# TIDA-01576_ADS8686S_ISO_Interface_Pg4-Is.net
KiCad netlist of a schematic drawn in Altium Designer
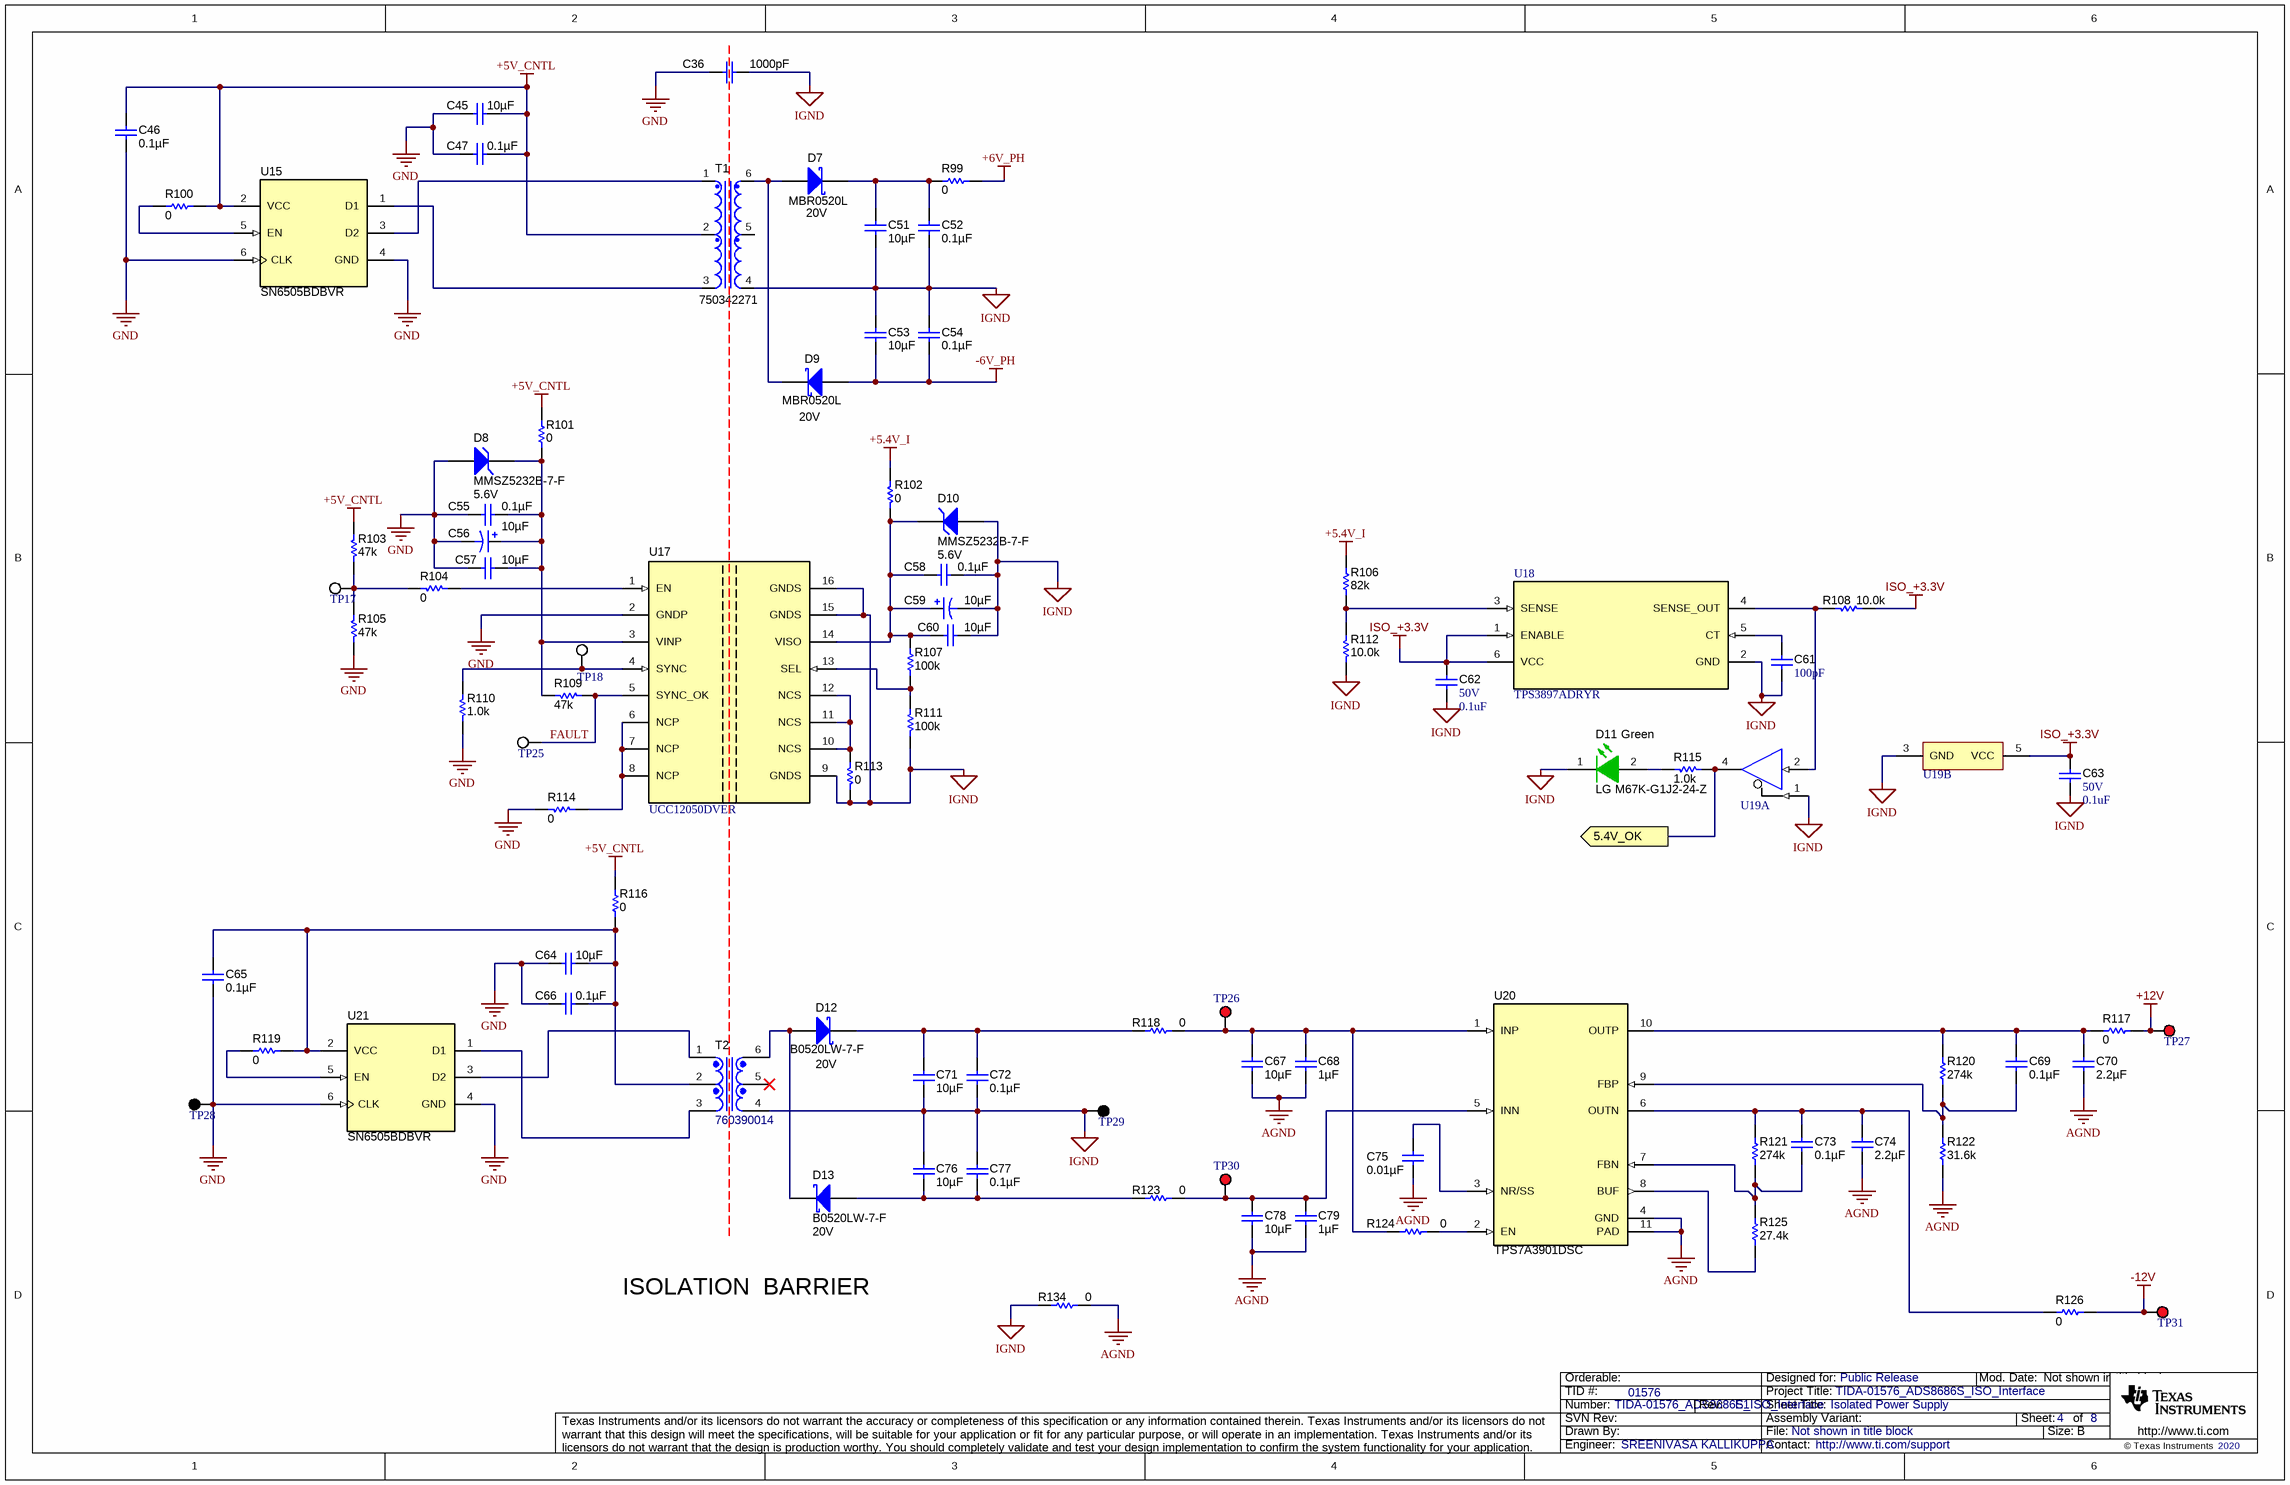
[diagram p0: TIDA-01576_ADS8686S_ISO_Interface_Pg4-Isolated Power Supply.SchDoc]

(export (version "E")
  (design (tool "Eeschema 10.0.6"))
  (components
    (comp (ref "C36")
      (value "1000pF")
      (footprint "CAP_200mil")
      (description "CAP CER 1000PF 1KV 10% RADIAL")
      (fields
        (field (name "PARTNUMBER") "S102K29Y5PN63J5R")
        (field (name "MANUFACTURER") "Vishay BC Components")
        (field (name "PUBLISHER") "Texas Instruments")
      )
      (libsource (lib "TI-INDIA-ALTIUM") (part "202R18W102KV4E"))
    )
    (comp (ref "C45")
      (value "~")
      (footprint "1210")
      (description "CAP, CERM, 10uF, 35V, +/-20%, X7R, 1210")
      (fields
        (field (name "PARTNUMBER") "GMK325AB7106MM-T")
        (field (name "VALUEDISPLAYED") "10µF")
        (field (name "MANUFACTURER") "Taiyo Yuden")
        (field (name "PUBLISHER") "Texas Instruments")
      )
      (libsource (lib "Capacitor_Ceramic") (part "GMK325AB7106MM-T"))
    )
    (comp (ref "C46")
      (value "~")
      (footprint "0603")
      (description "CAP, CERM, 0.1uF, 50V, +/-10%, X7R, 0603")
      (fields
        (field (name "PARTNUMBER") "C0603C104K5RACTU")
        (field (name "VALUEDISPLAYED") "0.1µF")
        (field (name "MANUFACTURER") "Kemet")
        (field (name "PUBLISHER") "Texas Instruments")
      )
      (libsource (lib "Capacitor_Ceramic") (part "C0603C104K5RACTU"))
    )
    (comp (ref "C47")
      (value "~")
      (footprint "0603")
      (description "CAP, CERM, 0.1uF, 50V, +/-10%, X7R, 0603")
      (fields
        (field (name "PARTNUMBER") "C0603C104K5RACTU")
        (field (name "VALUEDISPLAYED") "0.1µF")
        (field (name "MANUFACTURER") "Kemet")
        (field (name "PUBLISHER") "Texas Instruments")
      )
      (libsource (lib "Capacitor_Ceramic") (part "C0603C104K5RACTU"))
    )
    (comp (ref "C51")
      (value "~")
      (footprint "1210")
      (description "CAP, CERM, 10uF, 35V, +/-20%, X7R, 1210")
      (fields
        (field (name "PARTNUMBER") "GMK325AB7106MM-T")
        (field (name "VALUEDISPLAYED") "10µF")
        (field (name "MANUFACTURER") "Taiyo Yuden")
        (field (name "PUBLISHER") "Texas Instruments")
      )
      (libsource (lib "Capacitor_Ceramic") (part "GMK325AB7106MM-T"))
    )
    (comp (ref "C52")
      (value "~")
      (footprint "0603_HV")
      (description "CAP, CERM, 0.1uF, 50V, +/-10%, X7R, 0603")
      (fields
        (field (name "PARTNUMBER") "C0603C104K5RACTU")
        (field (name "VALUEDISPLAYED") "0.1µF")
        (field (name "MANUFACTURER") "Kemet")
        (field (name "PUBLISHER") "Texas Instruments")
      )
      (libsource (lib "Capacitor_Ceramic") (part "C0603C104K5RACTU"))
    )
    (comp (ref "C53")
      (value "~")
      (footprint "1210")
      (description "CAP, CERM, 10uF, 35V, +/-20%, X7R, 1210")
      (fields
        (field (name "PARTNUMBER") "GMK325AB7106MM-T")
        (field (name "VALUEDISPLAYED") "10µF")
        (field (name "MANUFACTURER") "Taiyo Yuden")
        (field (name "PUBLISHER") "Texas Instruments")
      )
      (libsource (lib "Capacitor_Ceramic") (part "GMK325AB7106MM-T"))
    )
    (comp (ref "C54")
      (value "~")
      (footprint "0603_HV")
      (description "CAP, CERM, 0.1uF, 50V, +/-10%, X7R, 0603")
      (fields
        (field (name "PARTNUMBER") "C0603C104K5RACTU")
        (field (name "VALUEDISPLAYED") "0.1µF")
        (field (name "MANUFACTURER") "Kemet")
        (field (name "PUBLISHER") "Texas Instruments")
      )
      (libsource (lib "Capacitor_Ceramic") (part "C0603C104K5RACTU"))
    )
    (comp (ref "C55")
      (value "C0603C104K5RACTU")
      (footprint "0603")
      (description "CAP, CERM, 0.1uF, 50V, +/-10%, X7R, 0603")
      (fields
        (field (name "VALUEDISPLAYED") "0.1µF")
        (field (name "MANUFACTURER") "Kemet")
        (field (name "PUBLISHER") "Texas Instruments")
      )
      (libsource (lib "Capacitor_Ceramic") (part "C0603C104K5RACTU"))
    )
    (comp (ref "C56")
      (value "T491B106K016AT")
      (footprint "3528-21")
      (description "CAP, TA, 10 µF, 16 V, +/- 10%, 2 ohm, SMD")
      (fields
        (field (name "MANUFACTURER") "Vishay-Sprague")
        (field (name "VALUEDISPLAYED") "10µF")
        (field (name "PUBLISHER") "Texas Instruments")
      )
      (libsource (lib "") (part "293D106X9016B2TE3_1"))
    )
    (comp (ref "C57")
      (value "GRM31CR61H106KA12L")
      (footprint "1206_180")
      (description "CAP, CERM, 10 µF, 50 V, +/- 10%, X5R, 1206")
      (fields
        (field (name "VALUEDISPLAYED") "10µF")
        (field (name "MANUFACTURER") "MuRata")
        (field (name "PUBLISHER") "Texas Instruments")
      )
      (libsource (lib "Capacitor_Ceramic") (part "GRM31CR61H106KA12L"))
    )
    (comp (ref "C58")
      (value "C0603C104K5RACTU")
      (footprint "0603")
      (description "CAP, CERM, 0.1uF, 50V, +/-10%, X7R, 0603")
      (fields
        (field (name "VALUEDISPLAYED") "0.1µF")
        (field (name "MANUFACTURER") "Kemet")
        (field (name "PUBLISHER") "Texas Instruments")
      )
      (libsource (lib "Capacitor_Ceramic") (part "C0603C104K5RACTU"))
    )
    (comp (ref "C59")
      (value "T491B106K016AT")
      (footprint "3528-21")
      (description "CAP, TA, 10 µF, 16 V, +/- 10%, 2 ohm, SMD")
      (fields
        (field (name "MANUFACTURER") "Vishay-Sprague")
        (field (name "VALUEDISPLAYED") "10µF")
        (field (name "PUBLISHER") "Texas Instruments")
      )
      (libsource (lib "Combo_Module_TIDA-00170") (part "293D106X9016B2TE3"))
    )
    (comp (ref "C60")
      (value "GRM31CR61H106KA12L")
      (footprint "1206_180")
      (description "CAP, CERM, 10 µF, 50 V, +/- 10%, X5R, 1206")
      (fields
        (field (name "VALUEDISPLAYED") "10µF")
        (field (name "MANUFACTURER") "MuRata")
        (field (name "PUBLISHER") "Texas Instruments")
      )
      (libsource (lib "Capacitor_Ceramic") (part "GRM31CR61H106KA12L"))
    )
    (comp (ref "C61")
      (value "06035A101FAT2A")
      (footprint "0603")
      (description "CAP, CERM, 100 pF, 50 V, +/- 1%, C0G/NP0, 0603")
      (fields
        (field (name "MANUFACTURER") "AVX")
        (field (name "VALUEDISPLAYED") "100pF")
        (field (name "PUBLISHER") "Texas Instruments")
      )
      (libsource (lib "Altium Vault - TI") (part "Capacitor"))
    )
    (comp (ref "C62")
      (value "C0603C104K5RACTU")
      (footprint "0603")
      (description "CAP, CERM, 0.1 uF, 50 V, +/- 10%, X7R, 0603")
      (fields
        (field (name "MANUFACTURER") "Kemet")
        (field (name "VDC_V") "50V")
        (field (name "VALUEDISPLAYED") "0.1uF")
        (field (name "PUBLISHER") "Texas Instruments")
      )
      (libsource (lib "Altium Vault - TI") (part "Capacitor"))
    )
    (comp (ref "C63")
      (value "C0603C104K5RACTU")
      (footprint "0603")
      (description "CAP, CERM, 0.1 uF, 50 V, +/- 10%, X7R, 0603")
      (fields
        (field (name "MANUFACTURER") "Kemet")
        (field (name "VDC_V") "50V")
        (field (name "VALUEDISPLAYED") "0.1uF")
        (field (name "PUBLISHER") "Texas Instruments")
      )
      (libsource (lib "Altium Vault - TI") (part "Capacitor"))
    )
    (comp (ref "C64")
      (value "~")
      (footprint "1210")
      (description "CAP, CERM, 10uF, 35V, +/-20%, X7R, 1210")
      (fields
        (field (name "PARTNUMBER") "GMK325AB7106MM-T")
        (field (name "VALUEDISPLAYED") "10µF")
        (field (name "MANUFACTURER") "Taiyo Yuden")
        (field (name "PUBLISHER") "Texas Instruments")
      )
      (libsource (lib "Capacitor_Ceramic") (part "GMK325AB7106MM-T"))
    )
    (comp (ref "C65")
      (value "~")
      (footprint "0603")
      (description "CAP, CERM, 0.1uF, 50V, +/-10%, X7R, 0603")
      (fields
        (field (name "PARTNUMBER") "C0603C104K5RACTU")
        (field (name "VALUEDISPLAYED") "0.1µF")
        (field (name "MANUFACTURER") "Kemet")
        (field (name "PUBLISHER") "Texas Instruments")
      )
      (libsource (lib "Capacitor_Ceramic") (part "C0603C104K5RACTU"))
    )
    (comp (ref "C66")
      (value "~")
      (footprint "0603")
      (description "CAP, CERM, 0.1uF, 50V, +/-10%, X7R, 0603")
      (fields
        (field (name "PARTNUMBER") "C0603C104K5RACTU")
        (field (name "VALUEDISPLAYED") "0.1µF")
        (field (name "MANUFACTURER") "Kemet")
        (field (name "PUBLISHER") "Texas Instruments")
      )
      (libsource (lib "Capacitor_Ceramic") (part "C0603C104K5RACTU"))
    )
    (comp (ref "C67")
      (value "C1210C106M5RACTU")
      (footprint "1206_180")
      (description "CAP, CERM, 10µF ±20% 50V Ceramic Capacitor X7R 1210")
      (fields
        (field (name "VALUEDISPLAYED") "10µF")
        (field (name "MANUFACTURER") "Kemet")
        (field (name "PUBLISHER") "Texas Instruments")
      )
      (libsource (lib "Capacitor_Ceramic") (part "CL31B106KBHNNNE"))
    )
    (comp (ref "C68")
      (value "C1608X7R1E105K080AB")
      (footprint "0603")
      (description "CAP, CERM,  1µF ±10% 25V Ceramic Capacitor X7R 0603")
      (fields
        (field (name "VALUEDISPLAYED") "1µF")
        (field (name "MANUFACTURER") "TDK")
        (field (name "PUBLISHER") "Texas Instruments")
      )
      (libsource (lib "Capacitor_Ceramic") (part "885012206052"))
    )
    (comp (ref "C69")
      (value "GMK107BJ104KAHT")
      (footprint "0603")
      (description "0.1µF ±10% 35V Ceramic Capacitor X5R 0603")
      (fields
        (field (name "VALUEDISPLAYED") "0.1µF")
        (field (name "MANUFACTURER") "Taiyo Yuden")
        (field (name "PUBLISHER") "Texas Instruments")
      )
      (libsource (lib "Capacitor_Ceramic") (part "06033C104JAT2A"))
    )
    (comp (ref "C70")
      (value "C0805C225K8RACTU")
      (footprint "0805_HV")
      (description "CAP, CERM, 2.2uF, 10V, +/-10%, X7R, 0805")
      (fields
        (field (name "VALUEDISPLAYED") "2.2µF")
        (field (name "MANUFACTURER") "Kemet")
        (field (name "PUBLISHER") "Texas Instruments")
      )
      (libsource (lib "Capacitor_Ceramic") (part "C0805C225K8RACTU"))
    )
    (comp (ref "C71")
      (value "~")
      (footprint "1210")
      (description "CAP, CERM, 10uF, 35V, +/-20%, X7R, 1210")
      (fields
        (field (name "PARTNUMBER") "GMK325AB7106MM-T")
        (field (name "VALUEDISPLAYED") "10µF")
        (field (name "MANUFACTURER") "Taiyo Yuden")
        (field (name "PUBLISHER") "Texas Instruments")
      )
      (libsource (lib "Capacitor_Ceramic") (part "GMK325AB7106MM-T"))
    )
    (comp (ref "C72")
      (value "~")
      (footprint "0603")
      (description "CAP, CERM, 0.1uF, 50V, +/-10%, X7R, 0603")
      (fields
        (field (name "PARTNUMBER") "C0603C104K5RACTU")
        (field (name "VALUEDISPLAYED") "0.1µF")
        (field (name "MANUFACTURER") "Kemet")
        (field (name "PUBLISHER") "Texas Instruments")
      )
      (libsource (lib "Capacitor_Ceramic") (part "C0603C104K5RACTU"))
    )
    (comp (ref "C73")
      (value "GMK107BJ104KAHT")
      (footprint "0603")
      (description "0.1µF ±10% 35V Ceramic Capacitor X5R 0603")
      (fields
        (field (name "VALUEDISPLAYED") "0.1µF")
        (field (name "MANUFACTURER") "Taiyo Yuden")
        (field (name "PUBLISHER") "Texas Instruments")
      )
      (libsource (lib "Capacitor_Ceramic") (part "06033C104JAT2A"))
    )
    (comp (ref "C74")
      (value "C0805C225K8RACTU")
      (footprint "0805_HV")
      (description "CAP, CERM, 2.2uF, 10V, +/-10%, X7R, 0805")
      (fields
        (field (name "VALUEDISPLAYED") "2.2µF")
        (field (name "MANUFACTURER") "Kemet")
        (field (name "PUBLISHER") "Texas Instruments")
      )
      (libsource (lib "Capacitor_Ceramic") (part "C0805C225K8RACTU"))
    )
    (comp (ref "C75")
      (value "GRM188R70J103KA01D")
      (footprint "0603")
      (description "CAP, CERM, 0.01 µF, 6.3 V, +/- 10%, X7R, 0603")
      (fields
        (field (name "VALUEDISPLAYED") "0.01µF")
        (field (name "MANUFACTURER") "MuRata")
        (field (name "PUBLISHER") "Texas Instruments")
      )
      (libsource (lib "Capacitor_Ceramic") (part "GRM188R70J103KA01D"))
    )
    (comp (ref "C76")
      (value "~")
      (footprint "1210")
      (description "CAP, CERM, 10uF, 35V, +/-20%, X7R, 1210")
      (fields
        (field (name "PARTNUMBER") "GMK325AB7106MM-T")
        (field (name "VALUEDISPLAYED") "10µF")
        (field (name "MANUFACTURER") "Taiyo Yuden")
        (field (name "PUBLISHER") "Texas Instruments")
      )
      (libsource (lib "Capacitor_Ceramic") (part "GMK325AB7106MM-T"))
    )
    (comp (ref "C77")
      (value "~")
      (footprint "0603")
      (description "CAP, CERM, 0.1uF, 50V, +/-10%, X7R, 0603")
      (fields
        (field (name "PARTNUMBER") "C0603C104K5RACTU")
        (field (name "VALUEDISPLAYED") "0.1µF")
        (field (name "MANUFACTURER") "Kemet")
        (field (name "PUBLISHER") "Texas Instruments")
      )
      (libsource (lib "Capacitor_Ceramic") (part "C0603C104K5RACTU"))
    )
    (comp (ref "C78")
      (value "C1210C106M5RACTU")
      (footprint "1206_180")
      (description "CAP, CERM, 10µF ±20% 50V Ceramic Capacitor X7R 1210")
      (fields
        (field (name "VALUEDISPLAYED") "10µF")
        (field (name "MANUFACTURER") "Kemet")
        (field (name "PUBLISHER") "Texas Instruments")
      )
      (libsource (lib "Capacitor_Ceramic") (part "CL31B106KBHNNNE"))
    )
    (comp (ref "C79")
      (value "C1608X7R1E105K080AB")
      (footprint "0603")
      (description "CAP, CERM,  1µF ±10% 25V Ceramic Capacitor X7R 0603")
      (fields
        (field (name "VALUEDISPLAYED") "1µF")
        (field (name "MANUFACTURER") "TDK")
        (field (name "PUBLISHER") "Texas Instruments")
      )
      (libsource (lib "Capacitor_Ceramic") (part "885012206052"))
    )
    (comp (ref "D7")
      (value "MBR0520L")
      (footprint "SOD-123")
      (description "Diode, Schottky, 20V, 0.5A, SOD-123")
      (fields
        (field (name "ALTIUM_VALUE") "20V")
        (field (name "MANUFACTURER") "Fairchild Semiconductor")
        (field (name "PUBLISHER") "Texas Instruments")
      )
      (libsource (lib "Diode") (part "MBR0520LT1G"))
    )
    (comp (ref "D8")
      (value "MMSZ5232B-7-F")
      (footprint "SOD-123")
      (description "Diode, Zener, 5.6 V, 500 mW, SOD-123")
      (fields
        (field (name "ALTIUM_VALUE") "5.6V")
        (field (name "MANUFACTURER") "Diodes Inc.")
        (field (name "SYMBOLCREATOR") "a0412235")
        (field (name "PUBLISHER") "Texas Instruments")
      )
      (libsource (lib "ZenerDiodes") (part "MMSZ5232B-7-F"))
    )
    (comp (ref "D9")
      (value "MBR0520L")
      (footprint "SOD-123")
      (description "Diode, Schottky, 20V, 0.5A, SOD-123")
      (fields
        (field (name "ALTIUM_VALUE") "20V")
        (field (name "MANUFACTURER") "Fairchild Semiconductor")
        (field (name "PUBLISHER") "Texas Instruments")
      )
      (libsource (lib "Diode") (part "MBR0520LT1G"))
    )
    (comp (ref "D10")
      (value "MMSZ5232B-7-F")
      (footprint "SOD-123")
      (description "Diode, Zener, 5.6 V, 500 mW, SOD-123")
      (fields
        (field (name "ALTIUM_VALUE") "5.6V")
        (field (name "MANUFACTURER") "Diodes Inc.")
        (field (name "SYMBOLCREATOR") "a0412235")
        (field (name "PUBLISHER") "Texas Instruments")
      )
      (libsource (lib "ZenerDiodes") (part "MMSZ5232B-7-F"))
    )
    (comp (ref "D11")
      (value "LG M67K-G1J2-24-Z")
      (footprint "LG_M67K_Green")
      (description "LED, Green, SMD")
      (fields
        (field (name "ALTIUM_VALUE") "Green")
        (field (name "MANUFACTURER") "OSRAM")
        (field (name "SYMBOLCREATOR") "Altium")
        (field (name "PUBLISHER") "Texas Instruments")
      )
      (libsource (lib "LED") (part "LG M67K-G1J2-24-Z"))
    )
    (comp (ref "D12")
      (value "B0520LW-7-F")
      (footprint "SOD-123")
      (description "Diode, Schottky, 20V, 0.5A, SOD-123")
      (fields
        (field (name "ALTIUM_VALUE") "20V")
        (field (name "MANUFACTURER") "Diodes Inc")
        (field (name "PUBLISHER") "Texas Instruments")
      )
      (libsource (lib "Diode") (part "MBR0520LT1G"))
    )
    (comp (ref "D13")
      (value "B0520LW-7-F")
      (footprint "SOD-123")
      (description "Diode, Schottky, 20V, 0.5A, SOD-123")
      (fields
        (field (name "ALTIUM_VALUE") "20V")
        (field (name "MANUFACTURER") "Diodes Inc")
        (field (name "PUBLISHER") "Texas Instruments")
      )
      (libsource (lib "Diode") (part "MBR0520LT1G"))
    )
    (comp (ref "R99")
      (value "CRCW06030000Z0EA")
      (footprint "0603")
      (description "RES, 0, 5%, 0.1 W, 0603")
      (fields
        (field (name "VALUEDISPLAYED") "0")
        (field (name "MANUFACTURER") "Vishay-Dale")
        (field (name "PUBLISHER") "Texas Instruments")
      )
      (libsource (lib "Resistor_0603") (part "CRCW06030000Z0EA"))
    )
    (comp (ref "R100")
      (value "0")
      (footprint "0603")
      (description "RES, 0 ohm, 5%, 0.1W, 0603")
      (fields
        (field (name "PARTNUMBER") "CRCW06030000Z0EA")
        (field (name "MANUFACTURER") "Vishay-Dale")
        (field (name "PUBLISHER") "Texas Instruments")
      )
      (libsource (lib "Resistor_0603") (part "CRCW06030000Z0EA"))
    )
    (comp (ref "R101")
      (value "CRCW06030000Z0EA")
      (footprint "0603")
      (description "RES, 0, 5%, 0.1 W, 0603")
      (fields
        (field (name "VALUEDISPLAYED") "0")
        (field (name "MANUFACTURER") "Vishay-Dale")
        (field (name "PUBLISHER") "Texas Instruments")
      )
      (libsource (lib "Resistor_0603") (part "CRCW06030000Z0EA"))
    )
    (comp (ref "R102")
      (value "CRCW06030000Z0EA")
      (footprint "0603")
      (description "RES, 0, 5%, 0.1 W, 0603")
      (fields
        (field (name "VALUEDISPLAYED") "0")
        (field (name "MANUFACTURER") "Vishay-Dale")
        (field (name "PUBLISHER") "Texas Instruments")
      )
      (libsource (lib "Resistor_0603") (part "CRCW06030000Z0EA"))
    )
    (comp (ref "R103")
      (value "RC0603JR-0747KL")
      (footprint "0603")
      (description "RES, 47 k, 5%, 0.1 W, 0603")
      (fields
        (field (name "VALUEDISPLAYED") "47k")
        (field (name "MANUFACTURER") "Yageo America")
        (field (name "PUBLISHER") "Texas Instruments")
      )
      (libsource (lib "Resistor_0603") (part "RC0603JR-0747KL"))
    )
    (comp (ref "R104")
      (value "CRCW06030000Z0EA")
      (footprint "0603")
      (description "RES, 0, 5%, 0.1 W, 0603")
      (fields
        (field (name "VALUEDISPLAYED") "0")
        (field (name "MANUFACTURER") "Vishay-Dale")
        (field (name "PUBLISHER") "Texas Instruments")
      )
      (libsource (lib "Resistor_0603") (part "CRCW06030000Z0EA"))
    )
    (comp (ref "R105")
      (value "RC0603JR-0747KL")
      (footprint "0603")
      (description "RES, 47 k, 5%, 0.1 W, 0603")
      (fields
        (field (name "VALUEDISPLAYED") "47k")
        (field (name "MANUFACTURER") "Yageo America")
        (field (name "PUBLISHER") "Texas Instruments")
      )
      (libsource (lib "Resistor_0603") (part "RC0603JR-0747KL"))
    )
    (comp (ref "R106")
      (value "CRCW060382K0JNEA")
      (footprint "0603")
      (description "RES, 82 k, 5%, 0.1 W, 0603")
      (fields
        (field (name "VALUEDISPLAYED") "82k")
        (field (name "MANUFACTURER") "Vishay-Dale")
        (field (name "PUBLISHER") "Texas Instruments")
      )
      (libsource (lib "Resistor_0603") (part "CRCW060382K0JNEA"))
    )
    (comp (ref "R107")
      (value "RC0603FR-07100KL")
      (footprint "0603")
      (description "RES, 100 k, 1%, 0.1 W, 0603")
      (fields
        (field (name "VALUEDISPLAYED") "100k")
        (field (name "MANUFACTURER") "Yageo America")
        (field (name "PUBLISHER") "Texas Instruments")
      )
      (libsource (lib "Resistor_0603") (part "RC0603FR-07100KL"))
    )
    (comp (ref "R108")
      (value "10.0k")
      (footprint "0603")
      (description "RES, 10.0k ohm, 1%, 0.1W, 0603")
      (fields
        (field (name "PARTNUMBER") "CRCW060310K0FKEA")
        (field (name "MANUFACTURER") "Vishay-Dale")
        (field (name "PUBLISHER") "Texas Instruments")
      )
      (libsource (lib "Resistor_0603") (part "CRCW060310K0FKEA"))
    )
    (comp (ref "R109")
      (value "RC0603JR-0747KL")
      (footprint "0603")
      (description "RES, 47 k, 5%, 0.1 W, 0603")
      (fields
        (field (name "VALUEDISPLAYED") "47k")
        (field (name "MANUFACTURER") "Yageo America")
        (field (name "PUBLISHER") "Texas Instruments")
      )
      (libsource (lib "Resistor_0603") (part "RC0603JR-0747KL"))
    )
    (comp (ref "R110")
      (value "RC0603JR-071KL")
      (footprint "0603")
      (description "RES, 1.0 k, 5%, 0.1 W, 0603")
      (fields
        (field (name "VALUEDISPLAYED") "1.0k")
        (field (name "MANUFACTURER") "Yageo America")
        (field (name "PUBLISHER") "Texas Instruments")
      )
      (libsource (lib "Resistor_0603") (part "RC0603JR-071KL"))
    )
    (comp (ref "R111")
      (value "RC0603FR-07100KL")
      (footprint "0603")
      (description "RES, 100 k, 1%, 0.1 W, 0603")
      (fields
        (field (name "VALUEDISPLAYED") "100k")
        (field (name "MANUFACTURER") "Yageo America")
        (field (name "PUBLISHER") "Texas Instruments")
      )
      (libsource (lib "Resistor_0603") (part "RC0603FR-07100KL"))
    )
    (comp (ref "R112")
      (value "10.0k")
      (footprint "0603")
      (description "RES, 10.0k ohm, 1%, 0.1W, 0603")
      (fields
        (field (name "PARTNUMBER") "CRCW060310K0FKEA")
        (field (name "MANUFACTURER") "Vishay-Dale")
        (field (name "PUBLISHER") "Texas Instruments")
      )
      (libsource (lib "Resistor_0603") (part "CRCW060310K0FKEA"))
    )
    (comp (ref "R113")
      (value "CRCW06030000Z0EA")
      (footprint "0603")
      (description "RES, 0, 5%, 0.1 W, 0603")
      (fields
        (field (name "VALUEDISPLAYED") "0")
        (field (name "MANUFACTURER") "Vishay-Dale")
        (field (name "PUBLISHER") "Texas Instruments")
      )
      (libsource (lib "Resistor_0603") (part "CRCW06030000Z0EA"))
    )
    (comp (ref "R114")
      (value "CRCW06030000Z0EA")
      (footprint "0603")
      (description "RES, 0, 5%, 0.1 W, 0603")
      (fields
        (field (name "VALUEDISPLAYED") "0")
        (field (name "MANUFACTURER") "Vishay-Dale")
        (field (name "PUBLISHER") "Texas Instruments")
      )
      (libsource (lib "Resistor_0603") (part "CRCW06030000Z0EA"))
    )
    (comp (ref "R115")
      (value "RC0603JR-071KL")
      (footprint "0603")
      (description "RES, 1.0 k, 5%, 0.1 W, 0603")
      (fields
        (field (name "VALUEDISPLAYED") "1.0k")
        (field (name "MANUFACTURER") "Yageo America")
        (field (name "PUBLISHER") "Texas Instruments")
      )
      (libsource (lib "Resistor_0603") (part "RC0603JR-071KL"))
    )
    (comp (ref "R116")
      (value "0")
      (footprint "0603")
      (description "RES, 0 ohm, 5%, 0.1W, 0603")
      (fields
        (field (name "PARTNUMBER") "CRCW06030000Z0EA")
        (field (name "MANUFACTURER") "Vishay-Dale")
        (field (name "PUBLISHER") "Texas Instruments")
      )
      (libsource (lib "Resistor_0603") (part "CRCW06030000Z0EA"))
    )
    (comp (ref "R117")
      (value "CRCW06030000Z0EA")
      (footprint "0603")
      (description "RES, 0, 5%, 0.1 W, 0603")
      (fields
        (field (name "VALUEDISPLAYED") "0")
        (field (name "MANUFACTURER") "Vishay-Dale")
        (field (name "PUBLISHER") "Texas Instruments")
      )
      (libsource (lib "Resistor_0603") (part "CRCW06030000Z0EA"))
    )
    (comp (ref "R118")
      (value "CRCW06030000Z0EA")
      (footprint "0603")
      (description "RES, 0, 5%, 0.1 W, 0603")
      (fields
        (field (name "VALUEDISPLAYED") "0")
        (field (name "MANUFACTURER") "Vishay-Dale")
        (field (name "PUBLISHER") "Texas Instruments")
      )
      (libsource (lib "Resistor_0603") (part "CRCW06030000Z0EA"))
    )
    (comp (ref "R119")
      (value "0")
      (footprint "0603")
      (description "RES, 0 ohm, 5%, 0.1W, 0603")
      (fields
        (field (name "PARTNUMBER") "CRCW06030000Z0EA")
        (field (name "MANUFACTURER") "Vishay-Dale")
        (field (name "PUBLISHER") "Texas Instruments")
      )
      (libsource (lib "Resistor_0603") (part "CRCW06030000Z0EA"))
    )
    (comp (ref "R120")
      (value "CRCW0603274KFKEA")
      (footprint "0603")
      (description "RES, 274 k, 1%, 0.1 W, 0603")
      (fields
        (field (name "VALUEDISPLAYED") "274k")
        (field (name "MANUFACTURER") "Vishay-Dale")
        (field (name "PUBLISHER") "Texas Instruments")
      )
      (libsource (lib "Resistor_0603") (part "CRCW0603274KFKEA"))
    )
    (comp (ref "R121")
      (value "CRCW0603274KFKEA")
      (footprint "0603")
      (description "RES, 274 k, 1%, 0.1 W, 0603")
      (fields
        (field (name "VALUEDISPLAYED") "274k")
        (field (name "MANUFACTURER") "Vishay-Dale")
        (field (name "PUBLISHER") "Texas Instruments")
      )
      (libsource (lib "Resistor_0603") (part "CRCW0603274KFKEA"))
    )
    (comp (ref "R122")
      (value "CRCW060331K6FKEA")
      (footprint "0603")
      (description "RES, 31.6 k, 1%, 0.1 W, 0603")
      (fields
        (field (name "VALUEDISPLAYED") "31.6k")
        (field (name "MANUFACTURER") "Vishay-Dale")
        (field (name "PUBLISHER") "Texas Instruments")
      )
      (libsource (lib "Resistor_0603") (part "CRCW060331K6FKEA"))
    )
    (comp (ref "R123")
      (value "CRCW06030000Z0EA")
      (footprint "0603")
      (description "RES, 0, 5%, 0.1 W, 0603")
      (fields
        (field (name "VALUEDISPLAYED") "0")
        (field (name "MANUFACTURER") "Vishay-Dale")
        (field (name "PUBLISHER") "Texas Instruments")
      )
      (libsource (lib "Resistor_0603") (part "CRCW06030000Z0EA"))
    )
    (comp (ref "R124")
      (value "CRCW06030000Z0EA")
      (footprint "0603")
      (description "RES, 0, 5%, 0.1 W, 0603")
      (fields
        (field (name "VALUEDISPLAYED") "0")
        (field (name "MANUFACTURER") "Vishay-Dale")
        (field (name "PUBLISHER") "Texas Instruments")
      )
      (libsource (lib "Resistor_0603") (part "CRCW06030000Z0EA"))
    )
    (comp (ref "R125")
      (value "CRCW060327K4FKEA")
      (footprint "0603")
      (description "RES, 27.4 k, 1%, 0.1 W, 0603")
      (fields
        (field (name "VALUEDISPLAYED") "27.4k")
        (field (name "MANUFACTURER") "Vishay-Dale")
        (field (name "PUBLISHER") "Texas Instruments")
      )
      (libsource (lib "Resistor_0603") (part "CRCW060327K4FKEA"))
    )
    (comp (ref "R126")
      (value "CRCW06030000Z0EA")
      (footprint "0603")
      (description "RES, 0, 5%, 0.1 W, 0603")
      (fields
        (field (name "VALUEDISPLAYED") "0")
        (field (name "MANUFACTURER") "Vishay-Dale")
        (field (name "PUBLISHER") "Texas Instruments")
      )
      (libsource (lib "Resistor_0603") (part "CRCW06030000Z0EA"))
    )
    (comp (ref "R134")
      (value "CRCW06030000Z0EA")
      (footprint "0603")
      (description "RES, 0, 5%, 0.1 W, 0603")
      (fields
        (field (name "VALUEDISPLAYED") "0")
        (field (name "MANUFACTURER") "Vishay-Dale")
        (field (name "PUBLISHER") "Texas Instruments")
      )
      (libsource (lib "Resistor_0603") (part "CRCW06030000Z0EA"))
    )
    (comp (ref "T1")
      (value "750342271")
      (footprint "760390015")
      (description "Transformer 469uH SMD")
      (fields (field (name "MANUFACTURER") "Wurth Electronics Midcom") (field (name "PUBLISHER") "TI"))
      (libsource (lib "Isolated current sensing") (part "TRNSFMR"))
    )
    (comp (ref "T2")
      (value "760390014")
      (footprint "Wurth_760390013")
      (description "Transformer, 475uH, SMT")
      (fields (field (name "MANUFACTURER") "Wurth Elektronik") (field (name "PUBLISHER") "Texas Instruments"))
      (libsource (lib "Altium Vault - TI") (part "Wurth_760390013"))
    )
    (comp (ref "TP17")
      (value "5002")
      (footprint "Keystone5002")
      (description "Test Point, Miniature, White, TH")
      (fields (field (name "MANUFACTURER") "Keystone") (field (name "PUBLISHER") "Texas Instruments"))
      (libsource (lib "Connectors_Keystone") (part "5002"))
    )
    (comp (ref "TP18")
      (value "5002")
      (footprint "Keystone5002")
      (description "Test Point, Miniature, White, TH")
      (fields (field (name "MANUFACTURER") "Keystone") (field (name "PUBLISHER") "Texas Instruments"))
      (libsource (lib "Connectors_Keystone") (part "5002"))
    )
    (comp (ref "TP25")
      (value "5002")
      (footprint "Keystone5002")
      (description "Test Point, Miniature, White, TH")
      (fields (field (name "MANUFACTURER") "Keystone") (field (name "PUBLISHER") "Texas Instruments"))
      (libsource (lib "Connectors_Keystone") (part "5002"))
    )
    (comp (ref "TP26")
      (value "5000")
      (footprint "Keystone5000")
      (description "Test Point, Miniature, Red, TH")
      (fields (field (name "MANUFACTURER") "Keystone") (field (name "PUBLISHER") "Texas Instruments"))
      (libsource (lib "Connectors_Keystone") (part "5000"))
    )
    (comp (ref "TP27")
      (value "5000")
      (footprint "Keystone5000")
      (description "Test Point, Miniature, Red, TH")
      (fields (field (name "MANUFACTURER") "Keystone") (field (name "PUBLISHER") "Texas Instruments"))
      (libsource (lib "Connectors_Keystone") (part "5000"))
    )
    (comp (ref "TP28")
      (value "5001")
      (footprint "Keystone5001")
      (description "Test Point, Miniature, Black, TH")
      (fields (field (name "MANUFACTURER") "Keystone") (field (name "PUBLISHER") "Texas Instruments"))
      (libsource (lib "Connectors_Keystone") (part "5001"))
    )
    (comp (ref "TP29")
      (value "5001")
      (footprint "Keystone5001")
      (description "Test Point, Miniature, Black, TH")
      (fields (field (name "MANUFACTURER") "Keystone") (field (name "PUBLISHER") "Texas Instruments"))
      (libsource (lib "Connectors_Keystone") (part "5001"))
    )
    (comp (ref "TP30")
      (value "5000")
      (footprint "Keystone5000")
      (description "Test Point, Miniature, Red, TH")
      (fields (field (name "MANUFACTURER") "Keystone") (field (name "PUBLISHER") "Texas Instruments"))
      (libsource (lib "Connectors_Keystone") (part "5000"))
    )
    (comp (ref "TP31")
      (value "5000")
      (footprint "Keystone5000")
      (description "Test Point, Miniature, Red, TH")
      (fields (field (name "MANUFACTURER") "Keystone") (field (name "PUBLISHER") "Texas Instruments"))
      (libsource (lib "Connectors_Keystone") (part "5000"))
    )
    (comp (ref "U15")
      (value "SN6505BDBVR")
      (footprint "DBV0006A_N")
      (description "LOW-NOISE 1A TRANSFORMER DRIVERS FOR ISOLATED POWER SUPPLIES, DBV0006A")
      (fields
        (field (name "ALTERNATE PARTNUMBER") "SN6505BDBVT")
        (field (name "MANUFACTURER") "Texas Instruments")
        (field (name "SYMBOLCREATOR") "Altium")
        (field (name "PUBLISHER") "Texas Instruments")
      )
      (libsource (lib "TI_Pre_RTM") (part "SN6505BDBVR"))
    )
    (comp (ref "U17")
      (value "UCC12050DVER")
      (footprint "DVE0016A")
      (description "500 mW, High-Efficiency, Low-Emissions, 5 kVRMS Isolated DC-DC Converter, DVE0016A (SO-MOD-16)")
      (fields
        (field (name "PARTNUMBER") "UCC12050DVER")
        (field (name "ALTERNATE PARTNUMBER") "UCC12050DVE")
        (field (name "MANUFACTURER") "Texas Instruments")
      )
      (libsource (lib "Altium Vault - TI") (part "UCC12050"))
    )
    (comp (ref "U18")
      (value "TPS3897ADRYR")
      (footprint "DRY0006A")
      (fields (field (name "MANUFACTURER") "Texas Instruments") (field (name "PARTNUMBER") "TPS3897ADRYR"))
      (libsource (lib "Altium Vault - TI") (part "TI-TPS3897DRY6"))
    )
    (comp (ref "U19")
      (value "SN74LVC1G125DCKR")
      (footprint "DCK0005A_N")
      (description "Single Bus Buffer Gate With 3-State Outputs, DCK0005A, LARGE T&R")
      (fields (field (name "MANUFACTURER") "Texas Instruments"))
      (libsource (lib "Altium Vault - TI") (part "TI-SN74AXXXX1X125-5"))
    )
    (comp (ref "U20")
      (value "TPS7A3901DSC")
      (footprint "DSC0010J")
      (fields
        (field (name "MANUFACTURER") "Texas Instruments")
        (field (name "SYMBOLCREATOR") "Altium")
        (field (name "PUBLISHER") "Texas Instruments")
      )
      (libsource (lib "TI_Pre_RTM") (part "TPS7A3901DSC"))
    )
    (comp (ref "U21")
      (value "SN6505BDBVR")
      (footprint "DBV0006A_N")
      (description "LOW-NOISE 1A TRANSFORMER DRIVERS FOR ISOLATED POWER SUPPLIES, DBV0006A")
      (fields
        (field (name "ALTERNATE PARTNUMBER") "SN6505BDBVT")
        (field (name "MANUFACTURER") "Texas Instruments")
        (field (name "SYMBOLCREATOR") "Altium")
        (field (name "PUBLISHER") "Texas Instruments")
      )
      (libsource (lib "TI_Pre_RTM") (part "SN6505BDBVR"))
    )
  )
  (nets
    (net (code "1") (name "+5.4V_I") (class "Default")
      (node (ref "R102") (pin "2") (pinfunction "2_2") (pintype "passive"))
      (node (ref "R106") (pin "1") (pinfunction "1_1") (pintype "passive"))
    )
    (net (code "2") (name "+5V_CNTL") (class "Default")
      (node (ref "C45") (pin "2") (pinfunction "2_2") (pintype "passive"))
      (node (ref "C46") (pin "2") (pinfunction "2_2") (pintype "passive"))
      (node (ref "C47") (pin "2") (pinfunction "2_2") (pintype "passive"))
      (node (ref "R100") (pin "1") (pinfunction "1_1") (pintype "passive"))
      (node (ref "R101") (pin "2") (pinfunction "2_2") (pintype "passive"))
      (node (ref "R103") (pin "2") (pinfunction "2_2") (pintype "passive"))
      (node (ref "R116") (pin "2") (pinfunction "2_2") (pintype "passive"))
      (node (ref "T1") (pin "2") (pinfunction "2_2") (pintype "passive"))
      (node (ref "U15") (pin "2") (pinfunction "VCC_2") (pintype "power_in"))
    )
    (net (code "3") (name "+6V_PH") (class "Default")
      (node (ref "R99") (pin "1") (pinfunction "1_1") (pintype "passive"))
    )
    (net (code "4") (name "+12V") (class "Default")
      (node (ref "R117") (pin "2") (pinfunction "2_2") (pintype "passive"))
      (node (ref "TP27") (pin "1") (pintype "passive"))
    )
    (net (code "5") (name "-6V_PH") (class "Default")
      (node (ref "C53") (pin "2") (pinfunction "2_2") (pintype "passive"))
      (node (ref "C54") (pin "2") (pinfunction "2_2") (pintype "passive"))
      (node (ref "D9") (pin "2") (pinfunction "A_2") (pintype "passive"))
    )
    (net (code "6") (name "-12V") (class "Default")
      (node (ref "R126") (pin "2") (pinfunction "2_2") (pintype "passive"))
      (node (ref "TP31") (pin "1") (pintype "passive"))
    )
    (net (code "7") (name "/5.4V_OK") (class "Default")
      (node (ref "R115") (pin "2") (pinfunction "2_2") (pintype "passive"))
      (node (ref "U19") (pin "4") (pinfunction "Y_4") (pintype "tri_state"))
    )
    (net (code "8") (name "/FAULT") (class "Default")
      (node (ref "R109") (pin "1") (pinfunction "1_1") (pintype "passive"))
      (node (ref "TP25") (pin "1") (pintype "passive"))
      (node (ref "U17") (pin "5") (pinfunction "SYNC_OK_5") (pintype "open_collector"))
    )
    (net (code "9") (name "AGND") (class "Default")
      (node (ref "C67") (pin "1") (pinfunction "1_1") (pintype "passive"))
      (node (ref "C68") (pin "2") (pinfunction "2_2") (pintype "passive"))
      (node (ref "C70") (pin "2") (pinfunction "2_2") (pintype "passive"))
      (node (ref "C74") (pin "2") (pinfunction "2_2") (pintype "passive"))
      (node (ref "C75") (pin "2") (pinfunction "2_2") (pintype "passive"))
      (node (ref "C78") (pin "1") (pinfunction "1_1") (pintype "passive"))
      (node (ref "C79") (pin "2") (pinfunction "2_2") (pintype "passive"))
      (node (ref "R122") (pin "1") (pinfunction "1_1") (pintype "passive"))
      (node (ref "R134") (pin "2") (pinfunction "2_2") (pintype "passive"))
      (node (ref "U20") (pin "11") (pinfunction "PAD_11") (pintype "power_in"))
      (node (ref "U20") (pin "4") (pinfunction "GND_4") (pintype "power_in"))
    )
    (net (code "10") (name "GND") (class "Default")
      (node (ref "C36") (pin "1") (pinfunction "1_1") (pintype "passive"))
      (node (ref "C45") (pin "1") (pinfunction "1_1") (pintype "passive"))
      (node (ref "C46") (pin "1") (pinfunction "1_1") (pintype "passive"))
      (node (ref "C47") (pin "1") (pinfunction "1_1") (pintype "passive"))
      (node (ref "C55") (pin "1") (pinfunction "1_1") (pintype "passive"))
      (node (ref "C56") (pin "2") (pinfunction "-_2") (pintype "passive"))
      (node (ref "C57") (pin "2") (pinfunction "2_2") (pintype "passive"))
      (node (ref "C64") (pin "1") (pinfunction "1_1") (pintype "passive"))
      (node (ref "C65") (pin "1") (pinfunction "1_1") (pintype "passive"))
      (node (ref "C66") (pin "1") (pinfunction "1_1") (pintype "passive"))
      (node (ref "D8") (pin "2") (pinfunction "A_2") (pintype "passive"))
      (node (ref "R105") (pin "1") (pinfunction "1_1") (pintype "passive"))
      (node (ref "R110") (pin "1") (pinfunction "1_1") (pintype "passive"))
      (node (ref "R114") (pin "2") (pinfunction "2_2") (pintype "passive"))
      (node (ref "TP28") (pin "1") (pintype "passive"))
      (node (ref "U15") (pin "4") (pinfunction "GND_4") (pintype "power_in"))
      (node (ref "U15") (pin "6") (pinfunction "CLK_6") (pintype "input"))
      (node (ref "U17") (pin "2") (pinfunction "GNDP_2") (pintype "power_in"))
      (node (ref "U21") (pin "4") (pinfunction "GND_4") (pintype "power_in"))
      (node (ref "U21") (pin "6") (pinfunction "CLK_6") (pintype "input"))
    )
    (net (code "11") (name "IGND") (class "Default")
      (node (ref "C36") (pin "2") (pinfunction "2_2") (pintype "passive"))
      (node (ref "C51") (pin "2") (pinfunction "2_2") (pintype "passive"))
      (node (ref "C52") (pin "2") (pinfunction "2_2") (pintype "passive"))
      (node (ref "C53") (pin "1") (pinfunction "1_1") (pintype "passive"))
      (node (ref "C54") (pin "1") (pinfunction "1_1") (pintype "passive"))
      (node (ref "C58") (pin "1") (pinfunction "1_1") (pintype "passive"))
      (node (ref "C59") (pin "2") (pinfunction "-_2") (pintype "passive"))
      (node (ref "C60") (pin "1") (pinfunction "1_1") (pintype "passive"))
      (node (ref "C61") (pin "2") (pinfunction "2_2") (pintype "passive"))
      (node (ref "C62") (pin "1") (pinfunction "1_1") (pintype "passive"))
      (node (ref "C63") (pin "2") (pinfunction "2_2") (pintype "passive"))
      (node (ref "C71") (pin "2") (pinfunction "2_2") (pintype "passive"))
      (node (ref "C72") (pin "2") (pinfunction "2_2") (pintype "passive"))
      (node (ref "C76") (pin "1") (pinfunction "1_1") (pintype "passive"))
      (node (ref "C77") (pin "1") (pinfunction "1_1") (pintype "passive"))
      (node (ref "D10") (pin "2") (pinfunction "A_2") (pintype "passive"))
      (node (ref "D11") (pin "1") (pinfunction "K_1") (pintype "passive"))
      (node (ref "R111") (pin "1") (pinfunction "1_1") (pintype "passive"))
      (node (ref "R112") (pin "2") (pinfunction "2_2") (pintype "passive"))
      (node (ref "R113") (pin "2") (pinfunction "2_2") (pintype "passive"))
      (node (ref "R134") (pin "1") (pinfunction "1_1") (pintype "passive"))
      (node (ref "T1") (pin "4") (pinfunction "4_4") (pintype "passive"))
      (node (ref "T2") (pin "4") (pinfunction "4_4") (pintype "passive"))
      (node (ref "TP29") (pin "1") (pintype "passive"))
      (node (ref "U17") (pin "15") (pinfunction "GNDS_15") (pintype "power_in"))
      (node (ref "U17") (pin "16") (pinfunction "GNDS_16") (pintype "passive"))
      (node (ref "U17") (pin "9") (pinfunction "GNDS_9") (pintype "power_in"))
      (node (ref "U18") (pin "2") (pinfunction "GND_2") (pintype "power_in"))
      (node (ref "U19") (pin "1") (pinfunction "~{OE}_1") (pintype "input"))
      (node (ref "U19") (pin "3") (pinfunction "GND_3") (pintype "power_in"))
    )
    (net (code "12") (name "ISO_+3.3V") (class "Default")
      (node (ref "C62") (pin "2") (pinfunction "2_2") (pintype "passive"))
      (node (ref "C63") (pin "1") (pinfunction "1_1") (pintype "passive"))
      (node (ref "R108") (pin "1") (pinfunction "1_1") (pintype "passive"))
      (node (ref "U18") (pin "1") (pinfunction "ENABLE_1") (pintype "input"))
      (node (ref "U18") (pin "6") (pinfunction "VCC_6") (pintype "power_in"))
      (node (ref "U19") (pin "5") (pinfunction "VCC_5") (pintype "power_in"))
    )
    (net (code "13") (name "Net-(C56-+)") (class "Default")
      (node (ref "C55") (pin "2") (pinfunction "2_2") (pintype "passive"))
      (node (ref "C56") (pin "1") (pinfunction "+_1") (pintype "passive"))
      (node (ref "C57") (pin "1") (pinfunction "1_1") (pintype "passive"))
      (node (ref "D8") (pin "1") (pinfunction "K_1") (pintype "passive"))
      (node (ref "R101") (pin "1") (pinfunction "1_1") (pintype "passive"))
      (node (ref "R109") (pin "2") (pinfunction "2_2") (pintype "passive"))
      (node (ref "U17") (pin "3") (pinfunction "VINP_3") (pintype "power_in"))
    )
    (net (code "14") (name "Net-(C59-+)") (class "Default")
      (node (ref "C58") (pin "2") (pinfunction "2_2") (pintype "passive"))
      (node (ref "C59") (pin "1") (pinfunction "+_1") (pintype "passive"))
      (node (ref "C60") (pin "2") (pinfunction "2_2") (pintype "passive"))
      (node (ref "D10") (pin "1") (pinfunction "K_1") (pintype "passive"))
      (node (ref "R102") (pin "1") (pinfunction "1_1") (pintype "passive"))
      (node (ref "R107") (pin "2") (pinfunction "2_2") (pintype "passive"))
      (node (ref "U17") (pin "14") (pinfunction "VISO_14") (pintype "power_in"))
    )
    (net (code "15") (name "Net-(D7-A)") (class "Default")
      (node (ref "D7") (pin "2") (pinfunction "A_2") (pintype "passive"))
      (node (ref "D9") (pin "1") (pinfunction "K_1") (pintype "passive"))
      (node (ref "T1") (pin "6") (pinfunction "6_6") (pintype "passive"))
    )
    (net (code "16") (name "Net-(D7-K)") (class "Default")
      (node (ref "C51") (pin "1") (pinfunction "1_1") (pintype "passive"))
      (node (ref "C52") (pin "1") (pinfunction "1_1") (pintype "passive"))
      (node (ref "D7") (pin "1") (pinfunction "K_1") (pintype "passive"))
      (node (ref "R99") (pin "2") (pinfunction "2_2") (pintype "passive"))
    )
    (net (code "17") (name "Net-(D11-A)") (class "Default")
      (node (ref "D11") (pin "2") (pinfunction "A_2") (pintype "passive"))
      (node (ref "R115") (pin "1") (pinfunction "1_1") (pintype "passive"))
    )
    (net (code "18") (name "Net-(D12-A)") (class "Default")
      (node (ref "D12") (pin "2") (pinfunction "A_2") (pintype "passive"))
      (node (ref "D13") (pin "1") (pinfunction "K_1") (pintype "passive"))
      (node (ref "T2") (pin "6") (pinfunction "6_6") (pintype "passive"))
    )
    (net (code "19") (name "Net-(D12-K)") (class "Default")
      (node (ref "C71") (pin "1") (pinfunction "1_1") (pintype "passive"))
      (node (ref "C72") (pin "1") (pinfunction "1_1") (pintype "passive"))
      (node (ref "D12") (pin "1") (pinfunction "K_1") (pintype "passive"))
      (node (ref "R118") (pin "1") (pinfunction "1_1") (pintype "passive"))
    )
    (net (code "20") (name "Net-(D13-A)") (class "Default")
      (node (ref "C76") (pin "2") (pinfunction "2_2") (pintype "passive"))
      (node (ref "C77") (pin "2") (pinfunction "2_2") (pintype "passive"))
      (node (ref "D13") (pin "2") (pinfunction "A_2") (pintype "passive"))
      (node (ref "R123") (pin "1") (pinfunction "1_1") (pintype "passive"))
    )
    (net (code "21") (name "Net-(R103-Pad1)") (class "Default")
      (node (ref "R103") (pin "1") (pinfunction "1_1") (pintype "passive"))
      (node (ref "R104") (pin "2") (pinfunction "2_2") (pintype "passive"))
      (node (ref "R105") (pin "2") (pinfunction "2_2") (pintype "passive"))
      (node (ref "TP17") (pin "1") (pintype "passive"))
    )
    (net (code "22") (name "Net-(R113-Pad1)") (class "Default")
      (node (ref "R113") (pin "1") (pinfunction "1_1") (pintype "passive"))
      (node (ref "U17") (pin "10") (pinfunction "NCS_10") (pintype "passive"))
      (node (ref "U17") (pin "11") (pinfunction "NCS_11") (pintype "passive"))
      (node (ref "U17") (pin "12") (pinfunction "NCS_12") (pintype "passive"))
    )
    (net (code "23") (name "Net-(R114-Pad1)") (class "Default")
      (node (ref "R114") (pin "1") (pinfunction "1_1") (pintype "passive"))
      (node (ref "U17") (pin "6") (pinfunction "NCP_6") (pintype "passive"))
      (node (ref "U17") (pin "7") (pinfunction "NCP_7") (pintype "passive"))
      (node (ref "U17") (pin "8") (pinfunction "NCP_8") (pintype "passive"))
    )
    (net (code "24") (name "Net-(U15-D1)") (class "Default")
      (node (ref "T1") (pin "3") (pinfunction "3_3") (pintype "passive"))
      (node (ref "U15") (pin "1") (pinfunction "D1_1") (pintype "open_collector"))
    )
    (net (code "25") (name "Net-(U15-D2)") (class "Default")
      (node (ref "T1") (pin "1") (pinfunction "1_1") (pintype "passive"))
      (node (ref "U15") (pin "3") (pinfunction "D2_3") (pintype "open_collector"))
    )
    (net (code "26") (name "Net-(U15-EN)") (class "Default")
      (node (ref "R100") (pin "2") (pinfunction "2_2") (pintype "passive"))
      (node (ref "U15") (pin "5") (pinfunction "EN_5") (pintype "input"))
    )
    (net (code "27") (name "Net-(U17-EN)") (class "Default")
      (node (ref "R104") (pin "1") (pinfunction "1_1") (pintype "passive"))
      (node (ref "U17") (pin "1") (pinfunction "EN_1") (pintype "input"))
    )
    (net (code "28") (name "Net-(U17-SEL)") (class "Default")
      (node (ref "R107") (pin "1") (pinfunction "1_1") (pintype "passive"))
      (node (ref "R111") (pin "2") (pinfunction "2_2") (pintype "passive"))
      (node (ref "U17") (pin "13") (pinfunction "SEL_13") (pintype "input"))
    )
    (net (code "29") (name "Net-(U17-SYNC)") (class "Default")
      (node (ref "R110") (pin "2") (pinfunction "2_2") (pintype "passive"))
      (node (ref "TP18") (pin "1") (pintype "passive"))
      (node (ref "U17") (pin "4") (pinfunction "SYNC_4") (pintype "input"))
    )
    (net (code "30") (name "Net-(U18-CT)") (class "Default")
      (node (ref "C61") (pin "1") (pinfunction "1_1") (pintype "passive"))
      (node (ref "U18") (pin "5") (pinfunction "CT_5") (pintype "input"))
    )
    (net (code "31") (name "Net-(U18-SENSE)") (class "Default")
      (node (ref "R106") (pin "2") (pinfunction "2_2") (pintype "passive"))
      (node (ref "R112") (pin "1") (pinfunction "1_1") (pintype "passive"))
      (node (ref "U18") (pin "3") (pinfunction "SENSE_3") (pintype "input"))
    )
    (net (code "32") (name "Net-(U18-SENSE_OUT)") (class "Default")
      (node (ref "R108") (pin "2") (pinfunction "2_2") (pintype "passive"))
      (node (ref "U18") (pin "4") (pinfunction "SENSE_OUT_4") (pintype "open_collector"))
      (node (ref "U19") (pin "2") (pinfunction "A_2") (pintype "input"))
    )
    (net (code "33") (name "Net-(U20-BUF)") (class "Default")
      (node (ref "R125") (pin "1") (pinfunction "1_1") (pintype "passive"))
      (node (ref "U20") (pin "8") (pinfunction "BUF_8") (pintype "output"))
    )
    (net (code "34") (name "Net-(U20-EN)") (class "Default")
      (node (ref "R124") (pin "2") (pinfunction "2_2") (pintype "passive"))
      (node (ref "U20") (pin "2") (pinfunction "EN_2") (pintype "input"))
    )
    (net (code "35") (name "Net-(U20-FBN)") (class "Default")
      (node (ref "C73") (pin "2") (pinfunction "2_2") (pintype "passive"))
      (node (ref "R121") (pin "1") (pinfunction "1_1") (pintype "passive"))
      (node (ref "R125") (pin "2") (pinfunction "2_2") (pintype "passive"))
      (node (ref "U20") (pin "7") (pinfunction "FBN_7") (pintype "input"))
    )
    (net (code "36") (name "Net-(U20-FBP)") (class "Default")
      (node (ref "C69") (pin "2") (pinfunction "2_2") (pintype "passive"))
      (node (ref "R120") (pin "1") (pinfunction "1_1") (pintype "passive"))
      (node (ref "R122") (pin "2") (pinfunction "2_2") (pintype "passive"))
      (node (ref "U20") (pin "9") (pinfunction "FBP_9") (pintype "input"))
    )
    (net (code "37") (name "Net-(U20-INN)") (class "Default")
      (node (ref "C78") (pin "2") (pinfunction "2_2") (pintype "passive"))
      (node (ref "C79") (pin "1") (pinfunction "1_1") (pintype "passive"))
      (node (ref "R123") (pin "2") (pinfunction "2_2") (pintype "passive"))
      (node (ref "TP30") (pin "1") (pintype "passive"))
      (node (ref "U20") (pin "5") (pinfunction "INN_5") (pintype "input"))
    )
    (net (code "38") (name "Net-(U20-INP)") (class "Default")
      (node (ref "C67") (pin "2") (pinfunction "2_2") (pintype "passive"))
      (node (ref "C68") (pin "1") (pinfunction "1_1") (pintype "passive"))
      (node (ref "R118") (pin "2") (pinfunction "2_2") (pintype "passive"))
      (node (ref "R124") (pin "1") (pinfunction "1_1") (pintype "passive"))
      (node (ref "TP26") (pin "1") (pintype "passive"))
      (node (ref "U20") (pin "1") (pinfunction "INP_1") (pintype "input"))
    )
    (net (code "39") (name "Net-(U20-NR{slash}SS)") (class "Default")
      (node (ref "C75") (pin "1") (pinfunction "1_1") (pintype "passive"))
      (node (ref "U20") (pin "3") (pinfunction "NR/SS_3") (pintype "input"))
    )
    (net (code "40") (name "Net-(U20-OUTN)") (class "Default")
      (node (ref "C73") (pin "1") (pinfunction "1_1") (pintype "passive"))
      (node (ref "C74") (pin "1") (pinfunction "1_1") (pintype "passive"))
      (node (ref "R121") (pin "2") (pinfunction "2_2") (pintype "passive"))
      (node (ref "R126") (pin "1") (pinfunction "1_1") (pintype "passive"))
      (node (ref "U20") (pin "6") (pinfunction "OUTN_6") (pintype "power_in"))
    )
    (net (code "41") (name "Net-(U20-OUTP)") (class "Default")
      (node (ref "C69") (pin "1") (pinfunction "1_1") (pintype "passive"))
      (node (ref "C70") (pin "1") (pinfunction "1_1") (pintype "passive"))
      (node (ref "R117") (pin "1") (pinfunction "1_1") (pintype "passive"))
      (node (ref "R120") (pin "2") (pinfunction "2_2") (pintype "passive"))
      (node (ref "U20") (pin "10") (pinfunction "OUTP_10") (pintype "power_in"))
    )
    (net (code "42") (name "Net-(U21-D1)") (class "Default")
      (node (ref "T2") (pin "3") (pinfunction "3_3") (pintype "passive"))
      (node (ref "U21") (pin "1") (pinfunction "D1_1") (pintype "open_collector"))
    )
    (net (code "43") (name "Net-(U21-D2)") (class "Default")
      (node (ref "T2") (pin "1") (pinfunction "1_1") (pintype "passive"))
      (node (ref "U21") (pin "3") (pinfunction "D2_3") (pintype "open_collector"))
    )
    (net (code "44") (name "Net-(U21-EN)") (class "Default")
      (node (ref "R119") (pin "2") (pinfunction "2_2") (pintype "passive"))
      (node (ref "U21") (pin "5") (pinfunction "EN_5") (pintype "input"))
    )
    (net (code "45") (name "Net-(U21-VCC)") (class "Default")
      (node (ref "C64") (pin "2") (pinfunction "2_2") (pintype "passive"))
      (node (ref "C65") (pin "2") (pinfunction "2_2") (pintype "passive"))
      (node (ref "C66") (pin "2") (pinfunction "2_2") (pintype "passive"))
      (node (ref "R116") (pin "1") (pinfunction "1_1") (pintype "passive"))
      (node (ref "R119") (pin "1") (pinfunction "1_1") (pintype "passive"))
      (node (ref "T2") (pin "2") (pinfunction "2_2") (pintype "passive"))
      (node (ref "U21") (pin "2") (pinfunction "VCC_2") (pintype "power_in"))
    )
    (net (code "46") (name "unconnected-(T1-Pad5)") (class "Default")
      (node (ref "T1") (pin "5") (pinfunction "5_5") (pintype "passive"))
    )
    (net (code "47") (name "unconnected-(T2-Pad5)") (class "Default")
      (node (ref "T2") (pin "5") (pinfunction "5_5") (pintype "passive+no_connect"))
    )
  )
)
